# Heater_ADC.net
KiCad netlist of a schematic drawn in Altium Designer
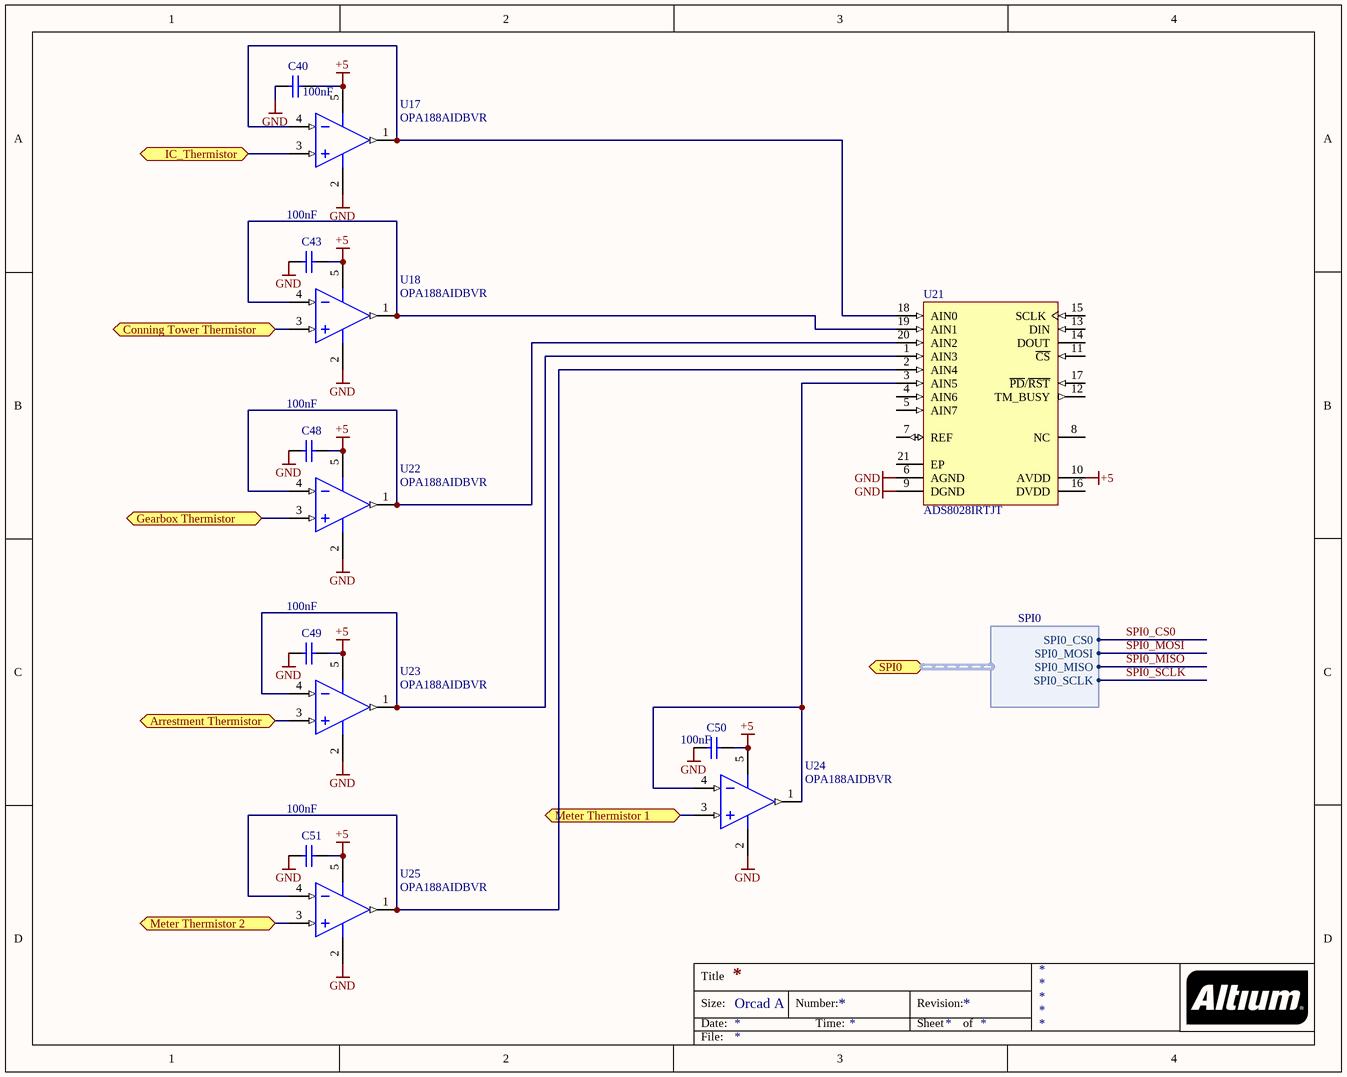
[diagram p0: Heater_ADC.SchDoc]

(export (version "E")
  (design (tool "Eeschema 10.0.6"))
  (components
    (comp (ref "C40")
      (value "~")
      (footprint "CAPC0402(1005)60_L")
      (fields
        (field (name "MANUFACTURER") "Kemet")
        (field (name "MANUFACTURER PART NUMBER") "C0402C104K4RACAUTO")
        (field (name "CAPACITANCE") "100nF")
        (field (name "TOLERANCE") "10%")
      )
      (libsource (lib "Altium Content Vault") (part "CMP-1034-01343-1"))
    )
    (comp (ref "C43")
      (value "~")
      (footprint "CAPC0402(1005)60_L")
      (fields
        (field (name "MANUFACTURER") "Kemet")
        (field (name "MANUFACTURER PART NUMBER") "C0402C104K4RACAUTO")
        (field (name "CAPACITANCE") "100nF")
        (field (name "TOLERANCE") "10%")
      )
      (libsource (lib "Altium Content Vault") (part "CMP-1034-01343-1"))
    )
    (comp (ref "C48")
      (value "~")
      (footprint "CAPC0402(1005)60_L")
      (fields
        (field (name "MANUFACTURER") "Kemet")
        (field (name "MANUFACTURER PART NUMBER") "C0402C104K4RACAUTO")
        (field (name "CAPACITANCE") "100nF")
        (field (name "TOLERANCE") "10%")
      )
      (libsource (lib "Altium Content Vault") (part "CMP-1034-01343-1"))
    )
    (comp (ref "C49")
      (value "~")
      (footprint "CAPC0402(1005)60_L")
      (fields
        (field (name "MANUFACTURER") "Kemet")
        (field (name "MANUFACTURER PART NUMBER") "C0402C104K4RACAUTO")
        (field (name "CAPACITANCE") "100nF")
        (field (name "TOLERANCE") "10%")
      )
      (libsource (lib "Altium Content Vault") (part "CMP-1034-01343-1"))
    )
    (comp (ref "C50")
      (value "~")
      (footprint "CAPC0402(1005)60_L")
      (fields
        (field (name "MANUFACTURER") "Kemet")
        (field (name "MANUFACTURER PART NUMBER") "C0402C104K4RACAUTO")
        (field (name "CAPACITANCE") "100nF")
        (field (name "TOLERANCE") "10%")
      )
      (libsource (lib "Altium Content Vault") (part "CMP-1034-01343-1"))
    )
    (comp (ref "C51")
      (value "~")
      (footprint "CAPC0402(1005)60_L")
      (fields
        (field (name "MANUFACTURER") "Kemet")
        (field (name "MANUFACTURER PART NUMBER") "C0402C104K4RACAUTO")
        (field (name "CAPACITANCE") "100nF")
        (field (name "TOLERANCE") "10%")
      )
      (libsource (lib "Altium Content Vault") (part "CMP-1034-01343-1"))
    )
    (comp (ref "U17")
      (value "OPA188AIDBVR")
      (footprint "DBV0005A_M")
      (fields (field (name "MANUFACTURER") "Texas Instruments"))
      (libsource (lib "Altium Content Vault") (part "CMP-0809-00005-2"))
    )
    (comp (ref "U18")
      (value "OPA188AIDBVR")
      (footprint "DBV0005A_M")
      (fields (field (name "MANUFACTURER") "Texas Instruments"))
      (libsource (lib "Altium Content Vault") (part "CMP-0809-00005-2"))
    )
    (comp (ref "U21")
      (value "ADS8028IRTJT")
      (footprint "TI-RTJ20-2600X2600TP_V")
      (fields (field (name "MANUFACTURER") "Texas Instruments"))
      (libsource (lib "Altium Content Vault") (part "CMP-0003-02168-1"))
    )
    (comp (ref "U22")
      (value "OPA188AIDBVR")
      (footprint "DBV0005A_M")
      (fields (field (name "MANUFACTURER") "Texas Instruments"))
      (libsource (lib "Altium Content Vault") (part "CMP-0809-00005-2"))
    )
    (comp (ref "U23")
      (value "OPA188AIDBVR")
      (footprint "DBV0005A_M")
      (fields (field (name "MANUFACTURER") "Texas Instruments"))
      (libsource (lib "Altium Content Vault") (part "CMP-0809-00005-2"))
    )
    (comp (ref "U24")
      (value "OPA188AIDBVR")
      (footprint "DBV0005A_M")
      (fields (field (name "MANUFACTURER") "Texas Instruments"))
      (libsource (lib "Altium Content Vault") (part "CMP-0809-00005-2"))
    )
    (comp (ref "U25")
      (value "OPA188AIDBVR")
      (footprint "DBV0005A_M")
      (fields (field (name "MANUFACTURER") "Texas Instruments"))
      (libsource (lib "Altium Content Vault") (part "CMP-0809-00005-2"))
    )
  )
  (nets
    (net (code "2") (name "+5") (class "Default")
      (node (ref "C40") (pin "2") (pinfunction "2_2") (pintype "passive"))
      (node (ref "C43") (pin "2") (pinfunction "2_2") (pintype "passive"))
      (node (ref "C48") (pin "2") (pinfunction "2_2") (pintype "passive"))
      (node (ref "C49") (pin "2") (pinfunction "2_2") (pintype "passive"))
      (node (ref "C50") (pin "2") (pinfunction "2_2") (pintype "passive"))
      (node (ref "C51") (pin "2") (pinfunction "2_2") (pintype "passive"))
      (node (ref "U17") (pin "5") (pinfunction "V+_5") (pintype "power_in"))
      (node (ref "U18") (pin "5") (pinfunction "V+_5") (pintype "power_in"))
      (node (ref "U21") (pin "10") (pinfunction "AVDD_10") (pintype "power_in"))
      (node (ref "U22") (pin "5") (pinfunction "V+_5") (pintype "power_in"))
      (node (ref "U23") (pin "5") (pinfunction "V+_5") (pintype "power_in"))
      (node (ref "U24") (pin "5") (pinfunction "V+_5") (pintype "power_in"))
      (node (ref "U25") (pin "5") (pinfunction "V+_5") (pintype "power_in"))
    )
    (net (code "3") (name "/Arrestment Thermistor") (class "Default")
      (node (ref "U23") (pin "3") (pinfunction "IN+_3") (pintype "input"))
    )
    (net (code "4") (name "/Conning Tower Thermistor") (class "Default")
      (node (ref "U18") (pin "3") (pinfunction "IN+_3") (pintype "input"))
    )
    (net (code "5") (name "/Gearbox Thermistor") (class "Default")
      (node (ref "U22") (pin "3") (pinfunction "IN+_3") (pintype "input"))
    )
    (net (code "6") (name "/IC_Thermistor") (class "Default")
      (node (ref "U17") (pin "3") (pinfunction "IN+_3") (pintype "input"))
    )
    (net (code "7") (name "/Meter Thermistor 1") (class "Default")
      (node (ref "U24") (pin "3") (pinfunction "IN+_3") (pintype "input"))
    )
    (net (code "8") (name "/Meter Thermistor 2") (class "Default")
      (node (ref "U25") (pin "3") (pinfunction "IN+_3") (pintype "input"))
    )
    (net (code "14") (name "GND") (class "Default")
      (node (ref "C40") (pin "1") (pinfunction "1_1") (pintype "passive"))
      (node (ref "C43") (pin "1") (pinfunction "1_1") (pintype "passive"))
      (node (ref "C48") (pin "1") (pinfunction "1_1") (pintype "passive"))
      (node (ref "C49") (pin "1") (pinfunction "1_1") (pintype "passive"))
      (node (ref "C50") (pin "1") (pinfunction "1_1") (pintype "passive"))
      (node (ref "C51") (pin "1") (pinfunction "1_1") (pintype "passive"))
      (node (ref "U17") (pin "2") (pinfunction "V-_2") (pintype "power_in"))
      (node (ref "U18") (pin "2") (pinfunction "V-_2") (pintype "power_in"))
      (node (ref "U21") (pin "6") (pinfunction "AGND_6") (pintype "power_in"))
      (node (ref "U21") (pin "9") (pinfunction "DGND_9") (pintype "power_in"))
      (node (ref "U22") (pin "2") (pinfunction "V-_2") (pintype "power_in"))
      (node (ref "U23") (pin "2") (pinfunction "V-_2") (pintype "power_in"))
      (node (ref "U24") (pin "2") (pinfunction "V-_2") (pintype "power_in"))
      (node (ref "U25") (pin "2") (pinfunction "V-_2") (pintype "power_in"))
    )
    (net (code "15") (name "Net-(U17-IN-)") (class "Default")
      (node (ref "U17") (pin "1") (pinfunction "OUT_1") (pintype "output"))
      (node (ref "U17") (pin "4") (pinfunction "IN-_4") (pintype "input"))
      (node (ref "U21") (pin "18") (pinfunction "AIN0_18") (pintype "input"))
    )
    (net (code "16") (name "Net-(U18-IN-)") (class "Default")
      (node (ref "U18") (pin "1") (pinfunction "OUT_1") (pintype "output"))
      (node (ref "U18") (pin "4") (pinfunction "IN-_4") (pintype "input"))
      (node (ref "U21") (pin "19") (pinfunction "AIN1_19") (pintype "input"))
    )
    (net (code "17") (name "Net-(U21-AIN2)") (class "Default")
      (node (ref "U21") (pin "20") (pinfunction "AIN2_20") (pintype "input"))
      (node (ref "U22") (pin "1") (pinfunction "OUT_1") (pintype "output"))
      (node (ref "U22") (pin "4") (pinfunction "IN-_4") (pintype "input"))
    )
    (net (code "18") (name "Net-(U21-AIN3)") (class "Default")
      (node (ref "U21") (pin "1") (pinfunction "AIN3_1") (pintype "input"))
      (node (ref "U23") (pin "1") (pinfunction "OUT_1") (pintype "output"))
      (node (ref "U23") (pin "4") (pinfunction "IN-_4") (pintype "input"))
    )
    (net (code "19") (name "Net-(U21-AIN4)") (class "Default")
      (node (ref "U21") (pin "2") (pinfunction "AIN4_2") (pintype "input"))
      (node (ref "U25") (pin "1") (pinfunction "OUT_1") (pintype "output"))
      (node (ref "U25") (pin "4") (pinfunction "IN-_4") (pintype "input"))
    )
    (net (code "20") (name "Net-(U21-AIN5)") (class "Default")
      (node (ref "U21") (pin "3") (pinfunction "AIN5_3") (pintype "input"))
      (node (ref "U24") (pin "1") (pinfunction "OUT_1") (pintype "output"))
      (node (ref "U24") (pin "4") (pinfunction "IN-_4") (pintype "input"))
    )
    (net (code "21") (name "unconnected-(U21-AIN6-Pad4)") (class "Default")
      (node (ref "U21") (pin "4") (pinfunction "AIN6_4") (pintype "input"))
    )
    (net (code "22") (name "unconnected-(U21-AIN7-Pad5)") (class "Default")
      (node (ref "U21") (pin "5") (pinfunction "AIN7_5") (pintype "input"))
    )
    (net (code "23") (name "unconnected-(U21-DIN-Pad13)") (class "Default")
      (node (ref "U21") (pin "13") (pinfunction "DIN_13") (pintype "input"))
    )
    (net (code "24") (name "unconnected-(U21-DOUT-Pad14)") (class "Default")
      (node (ref "U21") (pin "14") (pinfunction "DOUT_14") (pintype "tri_state"))
    )
    (net (code "25") (name "unconnected-(U21-DVDD-Pad16)") (class "Default")
      (node (ref "U21") (pin "16") (pinfunction "DVDD_16") (pintype "power_in"))
    )
    (net (code "26") (name "unconnected-(U21-EP-Pad21)") (class "Default")
      (node (ref "U21") (pin "21") (pinfunction "EP_21") (pintype "power_in"))
    )
    (net (code "27") (name "unconnected-(U21-NC-Pad8)") (class "Default")
      (node (ref "U21") (pin "8") (pinfunction "NC_8") (pintype "passive"))
    )
    (net (code "28") (name "unconnected-(U21-REF-Pad7)") (class "Default")
      (node (ref "U21") (pin "7") (pinfunction "REF_7") (pintype "bidirectional"))
    )
    (net (code "29") (name "unconnected-(U21-SCLK-Pad15)") (class "Default")
      (node (ref "U21") (pin "15") (pinfunction "SCLK_15") (pintype "input"))
    )
    (net (code "30") (name "unconnected-(U21-TM_BUSY-Pad12)") (class "Default")
      (node (ref "U21") (pin "12") (pinfunction "TM_BUSY_12") (pintype "output"))
    )
    (net (code "31") (name "unconnected-(U21-~{CS}-Pad11)") (class "Default")
      (node (ref "U21") (pin "11") (pinfunction "~{CS}_11") (pintype "input"))
    )
    (net (code "32") (name "unconnected-(U21-~{PD}{slash}~{RST}-Pad17)") (class "Default")
      (node (ref "U21") (pin "17") (pinfunction "~{PD}/~{RST}_17") (pintype "input"))
    )
  )
)
